# PG14_PS_BK500_BK501.net
KiCad netlist of a schematic drawn in Altium Designer
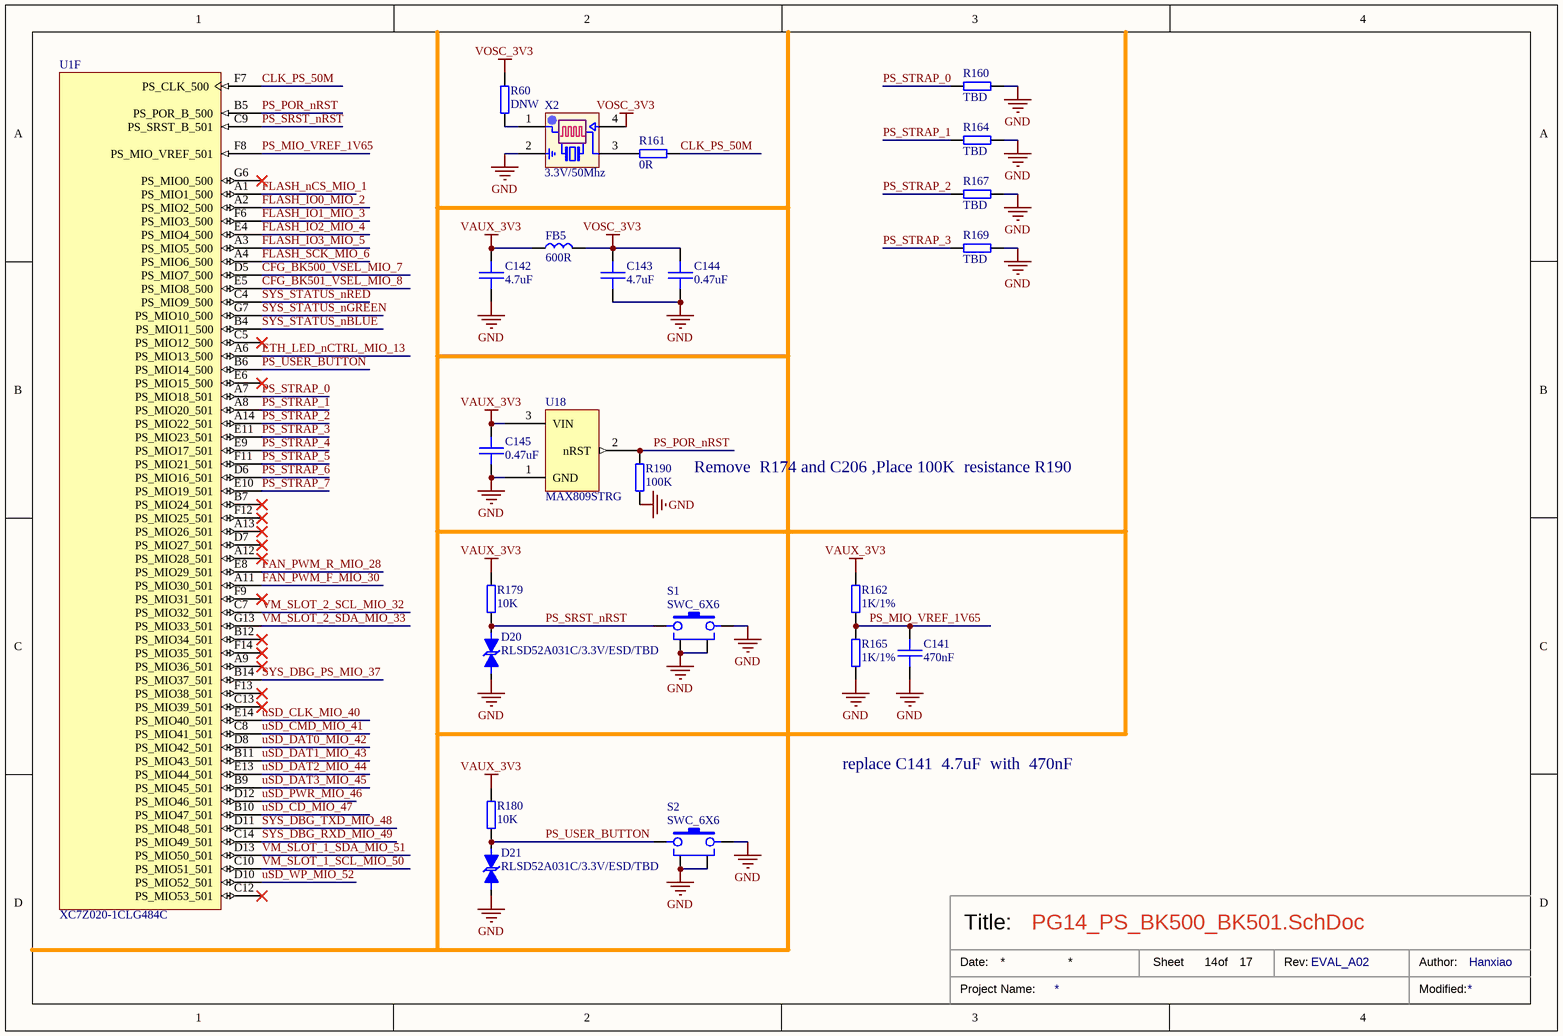
[diagram p0: PG14_PS_BK500_BK501.SchDoc]

(export (version "E")
  (design (tool "Eeschema 10.0.6"))
  (components
    (comp (ref "C141")
      (value "470nF")
      (footprint "SMT_C_0402")
      (description "Surface mount capacitor 0402")
      (libsource (lib "Vowstar_Basic_Device") (part "SMT_C_0402"))
    )
    (comp (ref "C142")
      (value "4.7uF")
      (footprint "SMT_C_0402")
      (description "Surface mount capacitor 0402")
      (libsource (lib "Vowstar_Basic_Device") (part "SMT_C_0402"))
    )
    (comp (ref "C143")
      (value "4.7uF")
      (footprint "SMT_C_0402")
      (description "Surface mount capacitor 0402")
      (libsource (lib "Vowstar_Basic_Device") (part "SMT_C_0402"))
    )
    (comp (ref "C144")
      (value "0.47uF")
      (footprint "SMT_C_0402")
      (description "Surface mount capacitor 0402")
      (libsource (lib "Vowstar_Basic_Device") (part "SMT_C_0402"))
    )
    (comp (ref "C145")
      (value "0.47uF")
      (footprint "SMT_C_0402")
      (description "Surface mount capacitor 0402")
      (libsource (lib "Vowstar_Basic_Device") (part "SMT_C_0402"))
    )
    (comp (ref "D20")
      (value "RLSD52A031C/3.3V/ESD/TBD")
      (footprint "SMT_DIODE_SOD_523")
      (description "Surface mount bidirectional TVS diode SOD-523(0603) Package")
      (libsource (lib "Vowstar_Basic_Device") (part "SMT_DIODE_TVS_B_SOD_523"))
    )
    (comp (ref "D21")
      (value "RLSD52A031C/3.3V/ESD/TBD")
      (footprint "SMT_DIODE_SOD_523")
      (description "Surface mount bidirectional TVS diode SOD-523(0603) Package")
      (libsource (lib "Vowstar_Basic_Device") (part "SMT_DIODE_TVS_B_SOD_523"))
    )
    (comp (ref "FB5")
      (value "600R")
      (footprint "SMT_FB_0402")
      (description "Surface mount ferrite beads 0603")
      (libsource (lib "Vowstar_Basic_Device") (part "SMT_FB_0603"))
    )
    (comp (ref "R60")
      (value "DNW")
      (footprint "SMT_R_0402")
      (description "Surface mount resistor 0402")
      (libsource (lib "Vowstar_Basic_Device") (part "SMT_R_0402"))
    )
    (comp (ref "R160")
      (value "TBD")
      (footprint "SMT_R_0402")
      (description "Surface mount resistor 0402")
      (libsource (lib "Vowstar_Basic_Device") (part "SMT_R_0402"))
    )
    (comp (ref "R161")
      (value "0R")
      (footprint "SMT_R_0402")
      (description "Surface mount resistor 0402")
      (libsource (lib "Vowstar_Basic_Device") (part "SMT_R_0402"))
    )
    (comp (ref "R162")
      (value "1K/1%")
      (footprint "SMT_R_0402")
      (description "Surface mount resistor 0402")
      (libsource (lib "Vowstar_Basic_Device") (part "SMT_R_0402"))
    )
    (comp (ref "R164")
      (value "TBD")
      (footprint "SMT_R_0402")
      (description "Surface mount resistor 0402")
      (libsource (lib "Vowstar_Basic_Device") (part "SMT_R_0402"))
    )
    (comp (ref "R165")
      (value "1K/1%")
      (footprint "SMT_R_0402")
      (description "Surface mount resistor 0402")
      (libsource (lib "Vowstar_Basic_Device") (part "SMT_R_0402"))
    )
    (comp (ref "R167")
      (value "TBD")
      (footprint "SMT_R_0402")
      (description "Surface mount resistor 0402")
      (libsource (lib "Vowstar_Basic_Device") (part "SMT_R_0402"))
    )
    (comp (ref "R169")
      (value "TBD")
      (footprint "SMT_R_0402")
      (description "Surface mount resistor 0402")
      (libsource (lib "Vowstar_Basic_Device") (part "SMT_R_0402"))
    )
    (comp (ref "R179")
      (value "10K")
      (footprint "SMT_R_0402")
      (description "Surface mount resistor 0402")
      (libsource (lib "Vowstar_Basic_Device") (part "SMT_R_0402"))
    )
    (comp (ref "R180")
      (value "10K")
      (footprint "SMT_R_0402")
      (description "Surface mount resistor 0402")
      (libsource (lib "Vowstar_Basic_Device") (part "SMT_R_0402"))
    )
    (comp (ref "R190")
      (value "100K")
      (footprint "SMT_R_0402")
      (description "Surface mount resistor 0402")
      (libsource (lib "Vowstar_Basic_Device") (part "SMT_R_0402"))
    )
    (comp (ref "S1")
      (value "SWC_6X6")
      (footprint "按键开关-6x6-卧式-直插")
      (description "按键开关-6x6-卧式-直插")
      (libsource (lib "Vowstar_Switch") (part "按键开关-6x6-卧式-直插"))
    )
    (comp (ref "S2")
      (value "SWC_6X6")
      (footprint "按键开关-6x6-卧式-直插")
      (description "按键开关-6x6-卧式-直插")
      (libsource (lib "Vowstar_Switch") (part "按键开关-6x6-卧式-直插"))
    )
    (comp (ref "U1")
      (value "XC7Z020-1CLG484C")
      (footprint "XC7Z020_CLG484")
      (fields (field (name "GENERIC PART NUMBER") "XC7Z020") (field (name "MANUFACTURER") "Xilinx"))
      (libsource (lib "Xilinx Zynq-7000") (part "XC7Z020-1CLG484C"))
    )
    (comp (ref "U18")
      (value "MAX809STRG")
      (footprint "SOT95P237X111-3L")
      (description "Very Low Supply Current\r\n3-Pin Microprocessor\r\nReset Monitors")
      (libsource (lib "LavasnowControllerHardware_EVAL_SCHLib_verA00") (part "MAX809STRG"))
    )
    (comp (ref "X2")
      (value "3.3V/50Mhz")
      (footprint "SMT_XTAL_3225")
      (description "Oscillator, Active crystal")
      (libsource (lib "Vowstar_Basic_Device") (part "SMT_XTAL_ACTIVE"))
    )
  )
  (nets
    (net (code "1") (name "/CFG_BK500_VSEL_MIO_7") (class "Default")
      (node (ref "U1") (pin "D5") (pinfunction "PS_MIO7_500_D5") (pintype "bidirectional"))
    )
    (net (code "2") (name "/CFG_BK501_VSEL_MIO_8") (class "Default")
      (node (ref "U1") (pin "E5") (pinfunction "PS_MIO8_500_E5") (pintype "bidirectional"))
    )
    (net (code "3") (name "/CLK_PS_50M") (class "Default")
      (node (ref "R161") (pin "2") (pinfunction "2_2") (pintype "passive"))
      (node (ref "U1") (pin "F7") (pinfunction "PS_CLK_500_F7") (pintype "input"))
    )
    (net (code "4") (name "/ETH_LED_nCTRL_MIO_13") (class "Default")
      (node (ref "U1") (pin "A6") (pinfunction "PS_MIO13_500_A6") (pintype "bidirectional"))
    )
    (net (code "5") (name "/FAN_PWM_F_MIO_30") (class "Default")
      (node (ref "U1") (pin "A11") (pinfunction "PS_MIO30_501_A11") (pintype "bidirectional"))
    )
    (net (code "6") (name "/FAN_PWM_R_MIO_28") (class "Default")
      (node (ref "U1") (pin "E8") (pinfunction "PS_MIO29_501_E8") (pintype "bidirectional"))
    )
    (net (code "7") (name "/FLASH_IO0_MIO_2") (class "Default")
      (node (ref "U1") (pin "A2") (pinfunction "PS_MIO2_500_A2") (pintype "bidirectional"))
    )
    (net (code "8") (name "/FLASH_IO1_MIO_3") (class "Default")
      (node (ref "U1") (pin "F6") (pinfunction "PS_MIO3_500_F6") (pintype "bidirectional"))
    )
    (net (code "9") (name "/FLASH_IO2_MIO_4") (class "Default")
      (node (ref "U1") (pin "E4") (pinfunction "PS_MIO4_500_E4") (pintype "bidirectional"))
    )
    (net (code "10") (name "/FLASH_IO3_MIO_5") (class "Default")
      (node (ref "U1") (pin "A3") (pinfunction "PS_MIO5_500_A3") (pintype "bidirectional"))
    )
    (net (code "11") (name "/FLASH_SCK_MIO_6") (class "Default")
      (node (ref "U1") (pin "A4") (pinfunction "PS_MIO6_500_A4") (pintype "bidirectional"))
    )
    (net (code "12") (name "/FLASH_nCS_MIO_1") (class "Default")
      (node (ref "U1") (pin "A1") (pinfunction "PS_MIO1_500_A1") (pintype "bidirectional"))
    )
    (net (code "13") (name "/PS_MIO_VREF_1V65") (class "Default")
      (node (ref "C141") (pin "1") (pinfunction "1_1") (pintype "passive"))
      (node (ref "R162") (pin "1") (pinfunction "1_1") (pintype "passive"))
      (node (ref "R165") (pin "2") (pinfunction "2_2") (pintype "passive"))
      (node (ref "U1") (pin "F8") (pinfunction "PS_MIO_VREF_501_F8") (pintype "input"))
    )
    (net (code "14") (name "/PS_POR_nRST") (class "Default")
      (node (ref "R190") (pin "2") (pinfunction "2_2") (pintype "passive"))
      (node (ref "U1") (pin "B5") (pinfunction "PS_POR_B_500_B5") (pintype "input"))
      (node (ref "U18") (pin "2") (pinfunction "nRST_2") (pintype "output"))
    )
    (net (code "15") (name "/PS_SRST_nRST") (class "Default")
      (node (ref "D20") (pin "1") (pinfunction "A_1") (pintype "passive"))
      (node (ref "R179") (pin "1") (pinfunction "1_1") (pintype "passive"))
      (node (ref "S1") (pin "1") (pinfunction "PIN1_1") (pintype "passive"))
      (node (ref "U1") (pin "C9") (pinfunction "PS_SRST_B_501_C9") (pintype "input"))
    )
    (net (code "16") (name "/PS_STRAP_0") (class "Default")
      (node (ref "R160") (pin "2") (pinfunction "2_2") (pintype "passive"))
      (node (ref "U1") (pin "A7") (pinfunction "PS_MIO18_501_A7") (pintype "bidirectional"))
    )
    (net (code "17") (name "/PS_STRAP_1") (class "Default")
      (node (ref "R164") (pin "2") (pinfunction "2_2") (pintype "passive"))
      (node (ref "U1") (pin "A8") (pinfunction "PS_MIO20_501_A8") (pintype "bidirectional"))
    )
    (net (code "18") (name "/PS_STRAP_2") (class "Default")
      (node (ref "R167") (pin "2") (pinfunction "2_2") (pintype "passive"))
      (node (ref "U1") (pin "A14") (pinfunction "PS_MIO22_501_A14") (pintype "bidirectional"))
    )
    (net (code "19") (name "/PS_STRAP_3") (class "Default")
      (node (ref "R169") (pin "2") (pinfunction "2_2") (pintype "passive"))
      (node (ref "U1") (pin "E11") (pinfunction "PS_MIO23_501_E11") (pintype "bidirectional"))
    )
    (net (code "20") (name "/PS_STRAP_4") (class "Default")
      (node (ref "U1") (pin "E9") (pinfunction "PS_MIO17_501_E9") (pintype "bidirectional"))
    )
    (net (code "21") (name "/PS_STRAP_5") (class "Default")
      (node (ref "U1") (pin "F11") (pinfunction "PS_MIO21_501_F11") (pintype "bidirectional"))
    )
    (net (code "22") (name "/PS_STRAP_6") (class "Default")
      (node (ref "U1") (pin "D6") (pinfunction "PS_MIO16_501_D6") (pintype "bidirectional"))
    )
    (net (code "23") (name "/PS_STRAP_7") (class "Default")
      (node (ref "U1") (pin "E10") (pinfunction "PS_MIO19_501_E10") (pintype "bidirectional"))
    )
    (net (code "24") (name "/PS_USER_BUTTON") (class "Default")
      (node (ref "D21") (pin "1") (pinfunction "A_1") (pintype "passive"))
      (node (ref "R180") (pin "1") (pinfunction "1_1") (pintype "passive"))
      (node (ref "S2") (pin "1") (pinfunction "PIN1_1") (pintype "passive"))
      (node (ref "U1") (pin "B6") (pinfunction "PS_MIO14_500_B6") (pintype "bidirectional"))
    )
    (net (code "25") (name "/SYS_DBG_PS_MIO_37") (class "Default")
      (node (ref "U1") (pin "B14") (pinfunction "PS_MIO37_501_B14") (pintype "bidirectional"))
    )
    (net (code "26") (name "/SYS_DBG_RXD_MIO_49") (class "Default")
      (node (ref "U1") (pin "C14") (pinfunction "PS_MIO49_501_C14") (pintype "bidirectional"))
    )
    (net (code "27") (name "/SYS_DBG_TXD_MIO_48") (class "Default")
      (node (ref "U1") (pin "D11") (pinfunction "PS_MIO48_501_D11") (pintype "bidirectional"))
    )
    (net (code "28") (name "/SYS_STATUS_nBLUE") (class "Default")
      (node (ref "U1") (pin "B4") (pinfunction "PS_MIO11_500_B4") (pintype "bidirectional"))
    )
    (net (code "29") (name "/SYS_STATUS_nGREEN") (class "Default")
      (node (ref "U1") (pin "G7") (pinfunction "PS_MIO10_500_G7") (pintype "bidirectional"))
    )
    (net (code "30") (name "/SYS_STATUS_nRED") (class "Default")
      (node (ref "U1") (pin "C4") (pinfunction "PS_MIO9_500_C4") (pintype "bidirectional"))
    )
    (net (code "31") (name "/VM_SLOT_1_SCL_MIO_50") (class "Default")
      (node (ref "U1") (pin "C10") (pinfunction "PS_MIO51_501_C10") (pintype "bidirectional"))
    )
    (net (code "32") (name "/VM_SLOT_1_SDA_MIO_51") (class "Default")
      (node (ref "U1") (pin "D13") (pinfunction "PS_MIO50_501_D13") (pintype "bidirectional"))
    )
    (net (code "33") (name "/VM_SLOT_2_SCL_MIO_32") (class "Default")
      (node (ref "U1") (pin "C7") (pinfunction "PS_MIO32_501_C7") (pintype "bidirectional"))
    )
    (net (code "34") (name "/VM_SLOT_2_SDA_MIO_33") (class "Default")
      (node (ref "U1") (pin "G13") (pinfunction "PS_MIO33_501_G13") (pintype "bidirectional"))
    )
    (net (code "35") (name "/uSD_CD_MIO_47") (class "Default")
      (node (ref "U1") (pin "B10") (pinfunction "PS_MIO47_501_B10") (pintype "bidirectional"))
    )
    (net (code "36") (name "/uSD_CLK_MIO_40") (class "Default")
      (node (ref "U1") (pin "E14") (pinfunction "PS_MIO40_501_E14") (pintype "bidirectional"))
    )
    (net (code "37") (name "/uSD_CMD_MIO_41") (class "Default")
      (node (ref "U1") (pin "C8") (pinfunction "PS_MIO41_501_C8") (pintype "bidirectional"))
    )
    (net (code "38") (name "/uSD_DAT0_MIO_42") (class "Default")
      (node (ref "U1") (pin "D8") (pinfunction "PS_MIO42_501_D8") (pintype "bidirectional"))
    )
    (net (code "39") (name "/uSD_DAT1_MIO_43") (class "Default")
      (node (ref "U1") (pin "B11") (pinfunction "PS_MIO43_501_B11") (pintype "bidirectional"))
    )
    (net (code "40") (name "/uSD_DAT2_MIO_44") (class "Default")
      (node (ref "U1") (pin "E13") (pinfunction "PS_MIO44_501_E13") (pintype "bidirectional"))
    )
    (net (code "41") (name "/uSD_DAT3_MIO_45") (class "Default")
      (node (ref "U1") (pin "B9") (pinfunction "PS_MIO45_501_B9") (pintype "bidirectional"))
    )
    (net (code "42") (name "/uSD_PWR_MIO_46") (class "Default")
      (node (ref "U1") (pin "D12") (pinfunction "PS_MIO46_501_D12") (pintype "bidirectional"))
    )
    (net (code "43") (name "/uSD_WP_MIO_52") (class "Default")
      (node (ref "U1") (pin "D10") (pinfunction "PS_MIO52_501_D10") (pintype "bidirectional"))
    )
    (net (code "44") (name "GND") (class "Default")
      (node (ref "C141") (pin "2") (pinfunction "2_2") (pintype "passive"))
      (node (ref "C142") (pin "2") (pinfunction "2_2") (pintype "passive"))
      (node (ref "C143") (pin "2") (pinfunction "2_2") (pintype "passive"))
      (node (ref "C144") (pin "2") (pinfunction "2_2") (pintype "passive"))
      (node (ref "C145") (pin "2") (pinfunction "2_2") (pintype "passive"))
      (node (ref "D20") (pin "2") (pinfunction "K_2") (pintype "passive"))
      (node (ref "D21") (pin "2") (pinfunction "K_2") (pintype "passive"))
      (node (ref "R160") (pin "1") (pinfunction "1_1") (pintype "passive"))
      (node (ref "R164") (pin "1") (pinfunction "1_1") (pintype "passive"))
      (node (ref "R165") (pin "1") (pinfunction "1_1") (pintype "passive"))
      (node (ref "R167") (pin "1") (pinfunction "1_1") (pintype "passive"))
      (node (ref "R169") (pin "1") (pinfunction "1_1") (pintype "passive"))
      (node (ref "R190") (pin "1") (pinfunction "1_1") (pintype "passive"))
      (node (ref "S1") (pin "2") (pinfunction "PIN2_2") (pintype "passive"))
      (node (ref "S1") (pin "3") (pinfunction "3_3") (pintype "passive"))
      (node (ref "S1") (pin "4") (pinfunction "4_4") (pintype "passive"))
      (node (ref "S2") (pin "2") (pinfunction "PIN2_2") (pintype "passive"))
      (node (ref "S2") (pin "3") (pinfunction "3_3") (pintype "passive"))
      (node (ref "S2") (pin "4") (pinfunction "4_4") (pintype "passive"))
      (node (ref "U18") (pin "1") (pinfunction "GND_1") (pintype "power_in"))
      (node (ref "X2") (pin "2") (pinfunction "GND_2") (pintype "passive"))
    )
    (net (code "45") (name "Net-(X2-CLKO)") (class "Default")
      (node (ref "R161") (pin "1") (pinfunction "1_1") (pintype "passive"))
      (node (ref "X2") (pin "3") (pinfunction "CLKO_3") (pintype "passive"))
    )
    (net (code "46") (name "Net-(X2-OE{slash}NC)") (class "Default")
      (node (ref "R60") (pin "1") (pinfunction "1_1") (pintype "passive"))
      (node (ref "X2") (pin "1") (pinfunction "OE/NC_1") (pintype "passive"))
    )
    (net (code "47") (name "VAUX_3V3") (class "Default")
      (node (ref "C142") (pin "1") (pinfunction "1_1") (pintype "passive"))
      (node (ref "C145") (pin "1") (pinfunction "1_1") (pintype "passive"))
      (node (ref "FB5") (pin "2") (pinfunction "2_2") (pintype "passive"))
      (node (ref "R162") (pin "2") (pinfunction "2_2") (pintype "passive"))
      (node (ref "R179") (pin "2") (pinfunction "2_2") (pintype "passive"))
      (node (ref "R180") (pin "2") (pinfunction "2_2") (pintype "passive"))
      (node (ref "U18") (pin "3") (pinfunction "VIN_3") (pintype "power_in"))
    )
    (net (code "48") (name "VOSC_3V3") (class "Default")
      (node (ref "C143") (pin "1") (pinfunction "1_1") (pintype "passive"))
      (node (ref "C144") (pin "1") (pinfunction "1_1") (pintype "passive"))
      (node (ref "FB5") (pin "1") (pinfunction "1_1") (pintype "passive"))
      (node (ref "R60") (pin "2") (pinfunction "2_2") (pintype "passive"))
      (node (ref "X2") (pin "4") (pinfunction "GND_4") (pintype "passive"))
    )
    (net (code "49") (name "unconnected-(U1F-PS_MIO0_500-PadG6)") (class "Default")
      (node (ref "U1") (pin "G6") (pinfunction "PS_MIO0_500_G6") (pintype "bidirectional+no_connect"))
    )
    (net (code "50") (name "unconnected-(U1F-PS_MIO12_500-PadC5)") (class "Default")
      (node (ref "U1") (pin "C5") (pinfunction "PS_MIO12_500_C5") (pintype "bidirectional+no_connect"))
    )
    (net (code "51") (name "unconnected-(U1F-PS_MIO15_500-PadE6)") (class "Default")
      (node (ref "U1") (pin "E6") (pinfunction "PS_MIO15_500_E6") (pintype "bidirectional+no_connect"))
    )
    (net (code "52") (name "unconnected-(U1F-PS_MIO24_501-PadB7)") (class "Default")
      (node (ref "U1") (pin "B7") (pinfunction "PS_MIO24_501_B7") (pintype "bidirectional+no_connect"))
    )
    (net (code "53") (name "unconnected-(U1F-PS_MIO25_501-PadF12)") (class "Default")
      (node (ref "U1") (pin "F12") (pinfunction "PS_MIO25_501_F12") (pintype "bidirectional+no_connect"))
    )
    (net (code "54") (name "unconnected-(U1F-PS_MIO26_501-PadA13)") (class "Default")
      (node (ref "U1") (pin "A13") (pinfunction "PS_MIO26_501_A13") (pintype "bidirectional+no_connect"))
    )
    (net (code "55") (name "unconnected-(U1F-PS_MIO27_501-PadD7)") (class "Default")
      (node (ref "U1") (pin "D7") (pinfunction "PS_MIO27_501_D7") (pintype "bidirectional+no_connect"))
    )
    (net (code "56") (name "unconnected-(U1F-PS_MIO28_501-PadA12)") (class "Default")
      (node (ref "U1") (pin "A12") (pinfunction "PS_MIO28_501_A12") (pintype "bidirectional+no_connect"))
    )
    (net (code "57") (name "unconnected-(U1F-PS_MIO31_501-PadF9)") (class "Default")
      (node (ref "U1") (pin "F9") (pinfunction "PS_MIO31_501_F9") (pintype "bidirectional+no_connect"))
    )
    (net (code "58") (name "unconnected-(U1F-PS_MIO34_501-PadB12)") (class "Default")
      (node (ref "U1") (pin "B12") (pinfunction "PS_MIO34_501_B12") (pintype "bidirectional+no_connect"))
    )
    (net (code "59") (name "unconnected-(U1F-PS_MIO35_501-PadF14)") (class "Default")
      (node (ref "U1") (pin "F14") (pinfunction "PS_MIO35_501_F14") (pintype "bidirectional+no_connect"))
    )
    (net (code "60") (name "unconnected-(U1F-PS_MIO36_501-PadA9)") (class "Default")
      (node (ref "U1") (pin "A9") (pinfunction "PS_MIO36_501_A9") (pintype "bidirectional+no_connect"))
    )
    (net (code "61") (name "unconnected-(U1F-PS_MIO38_501-PadF13)") (class "Default")
      (node (ref "U1") (pin "F13") (pinfunction "PS_MIO38_501_F13") (pintype "bidirectional+no_connect"))
    )
    (net (code "62") (name "unconnected-(U1F-PS_MIO39_501-PadC13)") (class "Default")
      (node (ref "U1") (pin "C13") (pinfunction "PS_MIO39_501_C13") (pintype "bidirectional+no_connect"))
    )
    (net (code "63") (name "unconnected-(U1F-PS_MIO53_501-PadC12)") (class "Default")
      (node (ref "U1") (pin "C12") (pinfunction "PS_MIO53_501_C12") (pintype "bidirectional+no_connect"))
    )
  )
)
